# power.net
KiCad netlist of a schematic drawn in Altium Designer
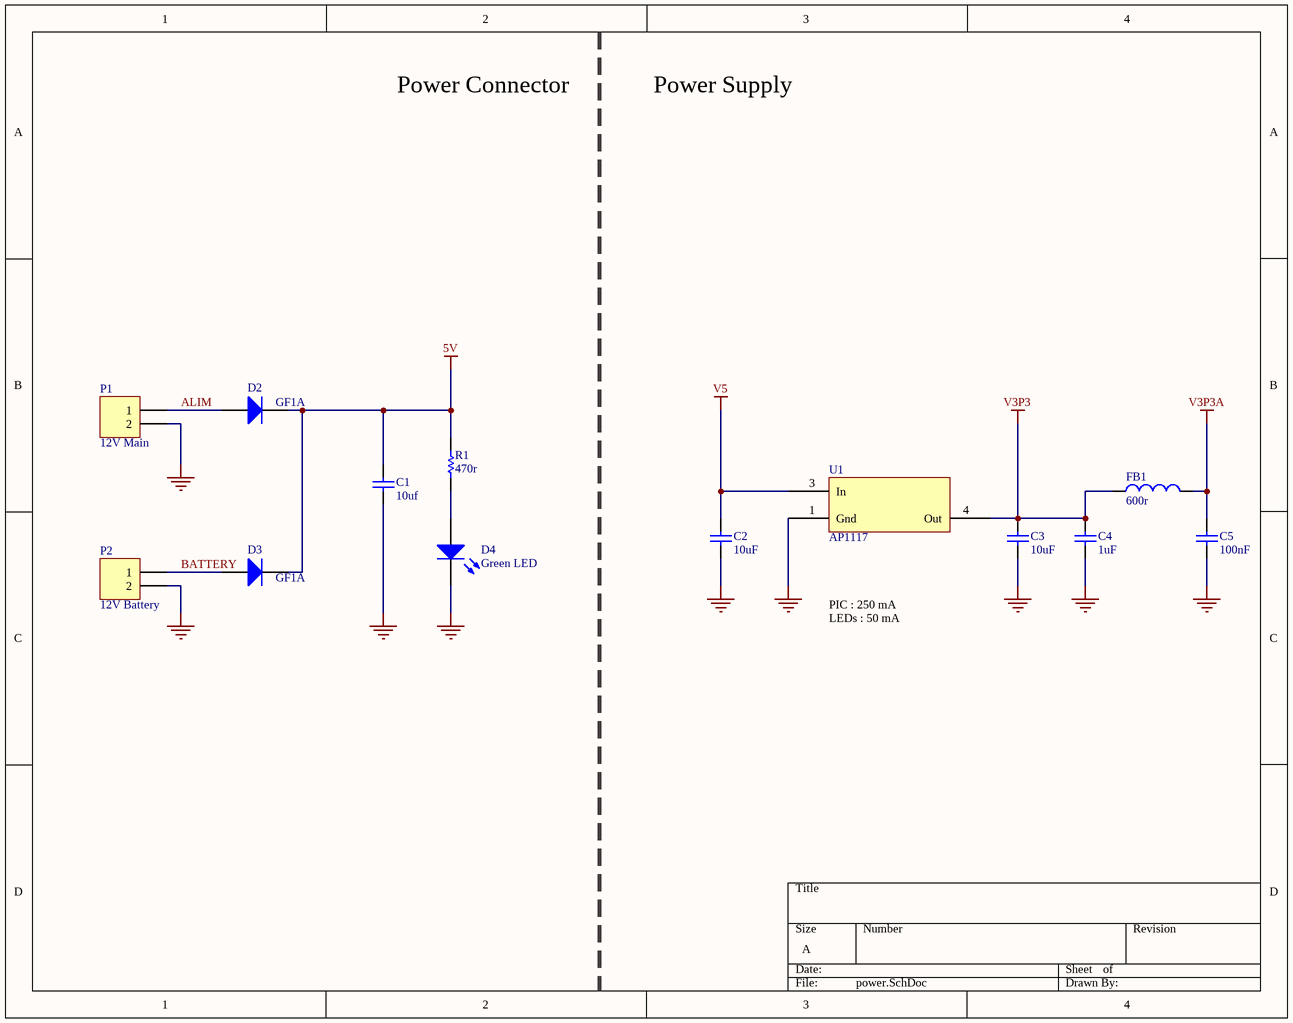
[diagram p0: power.SchDoc]

(export (version "E")
  (design (tool "Eeschema 10.0.6"))
  (components
    (comp (ref "C1")
      (value "10uf")
      (footprint "CAPC1608N")
      (description "Capacitor")
      (fields (field (name "PUBLISHER") "Altium Limited"))
      (libsource (lib "Miscellaneous Devices") (part "Cap"))
    )
    (comp (ref "C2")
      (value "10uF")
      (footprint "CAPC1608N")
      (description "Capacitor")
      (fields (field (name "PUBLISHER") "Altium Limited"))
      (libsource (lib "Miscellaneous Devices") (part "Cap"))
    )
    (comp (ref "C3")
      (value "10uF")
      (footprint "CAPC1608N")
      (description "Capacitor")
      (fields (field (name "PUBLISHER") "Altium Limited"))
      (libsource (lib "Miscellaneous Devices") (part "Cap"))
    )
    (comp (ref "C4")
      (value "1uF")
      (footprint "CAPC1608N")
      (description "Capacitor")
      (fields (field (name "PUBLISHER") "Altium Limited"))
      (libsource (lib "Miscellaneous Devices") (part "Cap"))
    )
    (comp (ref "C5")
      (value "100nF")
      (footprint "CAPC1608N")
      (description "Capacitor")
      (fields (field (name "PUBLISHER") "Altium Limited"))
      (libsource (lib "Miscellaneous Devices") (part "Cap"))
    )
    (comp (ref "D2")
      (value "GF1A")
      (footprint "SMA/DO-214AC_21")
      (description "Default Diode")
      (fields (field (name "PUBLISHER") "Altium Limited"))
      (libsource (lib "Miscellaneous Devices") (part "Diode"))
    )
    (comp (ref "D3")
      (value "GF1A")
      (footprint "SMA/DO-214AC_21")
      (description "Default Diode")
      (fields (field (name "PUBLISHER") "Altium Limited"))
      (libsource (lib "Miscellaneous Devices") (part "Diode"))
    )
    (comp (ref "D4")
      (value "Green LED")
      (footprint "LED 0805")
      (description "Typical INFRARED GaAs LED")
      (fields (field (name "PUBLISHER") "Altium Limited"))
      (libsource (lib "Miscellaneous Devices") (part "LED0"))
    )
    (comp (ref "FB1")
      (value "600r")
      (footprint "0402-A")
      (description "Inductor")
      (fields (field (name "PUBLISHER") "Altium Limited"))
      (libsource (lib "Miscellaneous Devices") (part "Inductor"))
    )
    (comp (ref "P1")
      (value "12V Main")
      (footprint "PHOENIX_1985195")
      (description "Header, 2-Pin")
      (fields (field (name "PUBLISHER") "Altium Limited"))
      (libsource (lib "Miscellaneous Connectors") (part "Header 2"))
    )
    (comp (ref "P2")
      (value "12V Battery")
      (footprint "PHOENIX_1985195")
      (description "Header, 2-Pin")
      (fields (field (name "PUBLISHER") "Altium Limited"))
      (libsource (lib "Miscellaneous Connectors") (part "Header 2"))
    )
    (comp (ref "R1")
      (value "470r")
      (footprint "RESC1608N")
      (description "Resistor")
      (fields (field (name "PUBLISHER") "Altium Limited"))
      (libsource (lib "Miscellaneous Devices") (part "Res1"))
    )
    (comp (ref "U1") (value "AP1117") (footprint "TD03B_N") (libsource (lib "tp2") (part "AP1117")))
  )
  (nets
    (net (code "1") (name "/ALIM") (class "Default")
      (node (ref "D2") (pin "1") (pinfunction "A_1") (pintype "passive"))
      (node (ref "P1") (pin "1") (pinfunction "1_1") (pintype "passive"))
    )
    (net (code "2") (name "/BATTERY") (class "Default")
      (node (ref "D3") (pin "1") (pinfunction "A_1") (pintype "passive"))
      (node (ref "P2") (pin "1") (pinfunction "1_1") (pintype "passive"))
    )
    (net (code "3") (name "5V") (class "Default")
      (node (ref "C1") (pin "2") (pinfunction "2_2") (pintype "passive"))
      (node (ref "D2") (pin "2") (pinfunction "K_2") (pintype "passive"))
      (node (ref "D3") (pin "2") (pinfunction "K_2") (pintype "passive"))
      (node (ref "R1") (pin "2") (pinfunction "2_2") (pintype "passive"))
    )
    (net (code "4") (name "GND") (class "Default")
      (node (ref "C1") (pin "1") (pinfunction "1_1") (pintype "passive"))
      (node (ref "C2") (pin "1") (pinfunction "1_1") (pintype "passive"))
      (node (ref "C3") (pin "1") (pinfunction "1_1") (pintype "passive"))
      (node (ref "C4") (pin "1") (pinfunction "1_1") (pintype "passive"))
      (node (ref "C5") (pin "1") (pinfunction "1_1") (pintype "passive"))
      (node (ref "D4") (pin "2") (pinfunction "K_2") (pintype "passive"))
      (node (ref "P1") (pin "2") (pinfunction "2_2") (pintype "passive"))
      (node (ref "P2") (pin "2") (pinfunction "2_2") (pintype "passive"))
      (node (ref "U1") (pin "1") (pinfunction "Gnd_1") (pintype "power_in"))
    )
    (net (code "5") (name "Net-(D4-A)") (class "Default")
      (node (ref "D4") (pin "1") (pinfunction "A_1") (pintype "passive"))
      (node (ref "R1") (pin "1") (pinfunction "1_1") (pintype "passive"))
    )
    (net (code "6") (name "V3P3") (class "Default")
      (node (ref "C3") (pin "2") (pinfunction "2_2") (pintype "passive"))
      (node (ref "C4") (pin "2") (pinfunction "2_2") (pintype "passive"))
      (node (ref "FB1") (pin "1") (pinfunction "1_1") (pintype "passive"))
      (node (ref "U1") (pin "4") (pinfunction "Out_4") (pintype "power_in"))
    )
    (net (code "7") (name "V3P3A") (class "Default")
      (node (ref "C5") (pin "2") (pinfunction "2_2") (pintype "passive"))
      (node (ref "FB1") (pin "2") (pinfunction "2_2") (pintype "passive"))
    )
    (net (code "8") (name "V5") (class "Default")
      (node (ref "C2") (pin "2") (pinfunction "2_2") (pintype "passive"))
      (node (ref "U1") (pin "3") (pinfunction "In_3") (pintype "power_in"))
    )
  )
)
